# Microcontroller.net
KiCad netlist of a schematic drawn in Altium Designer
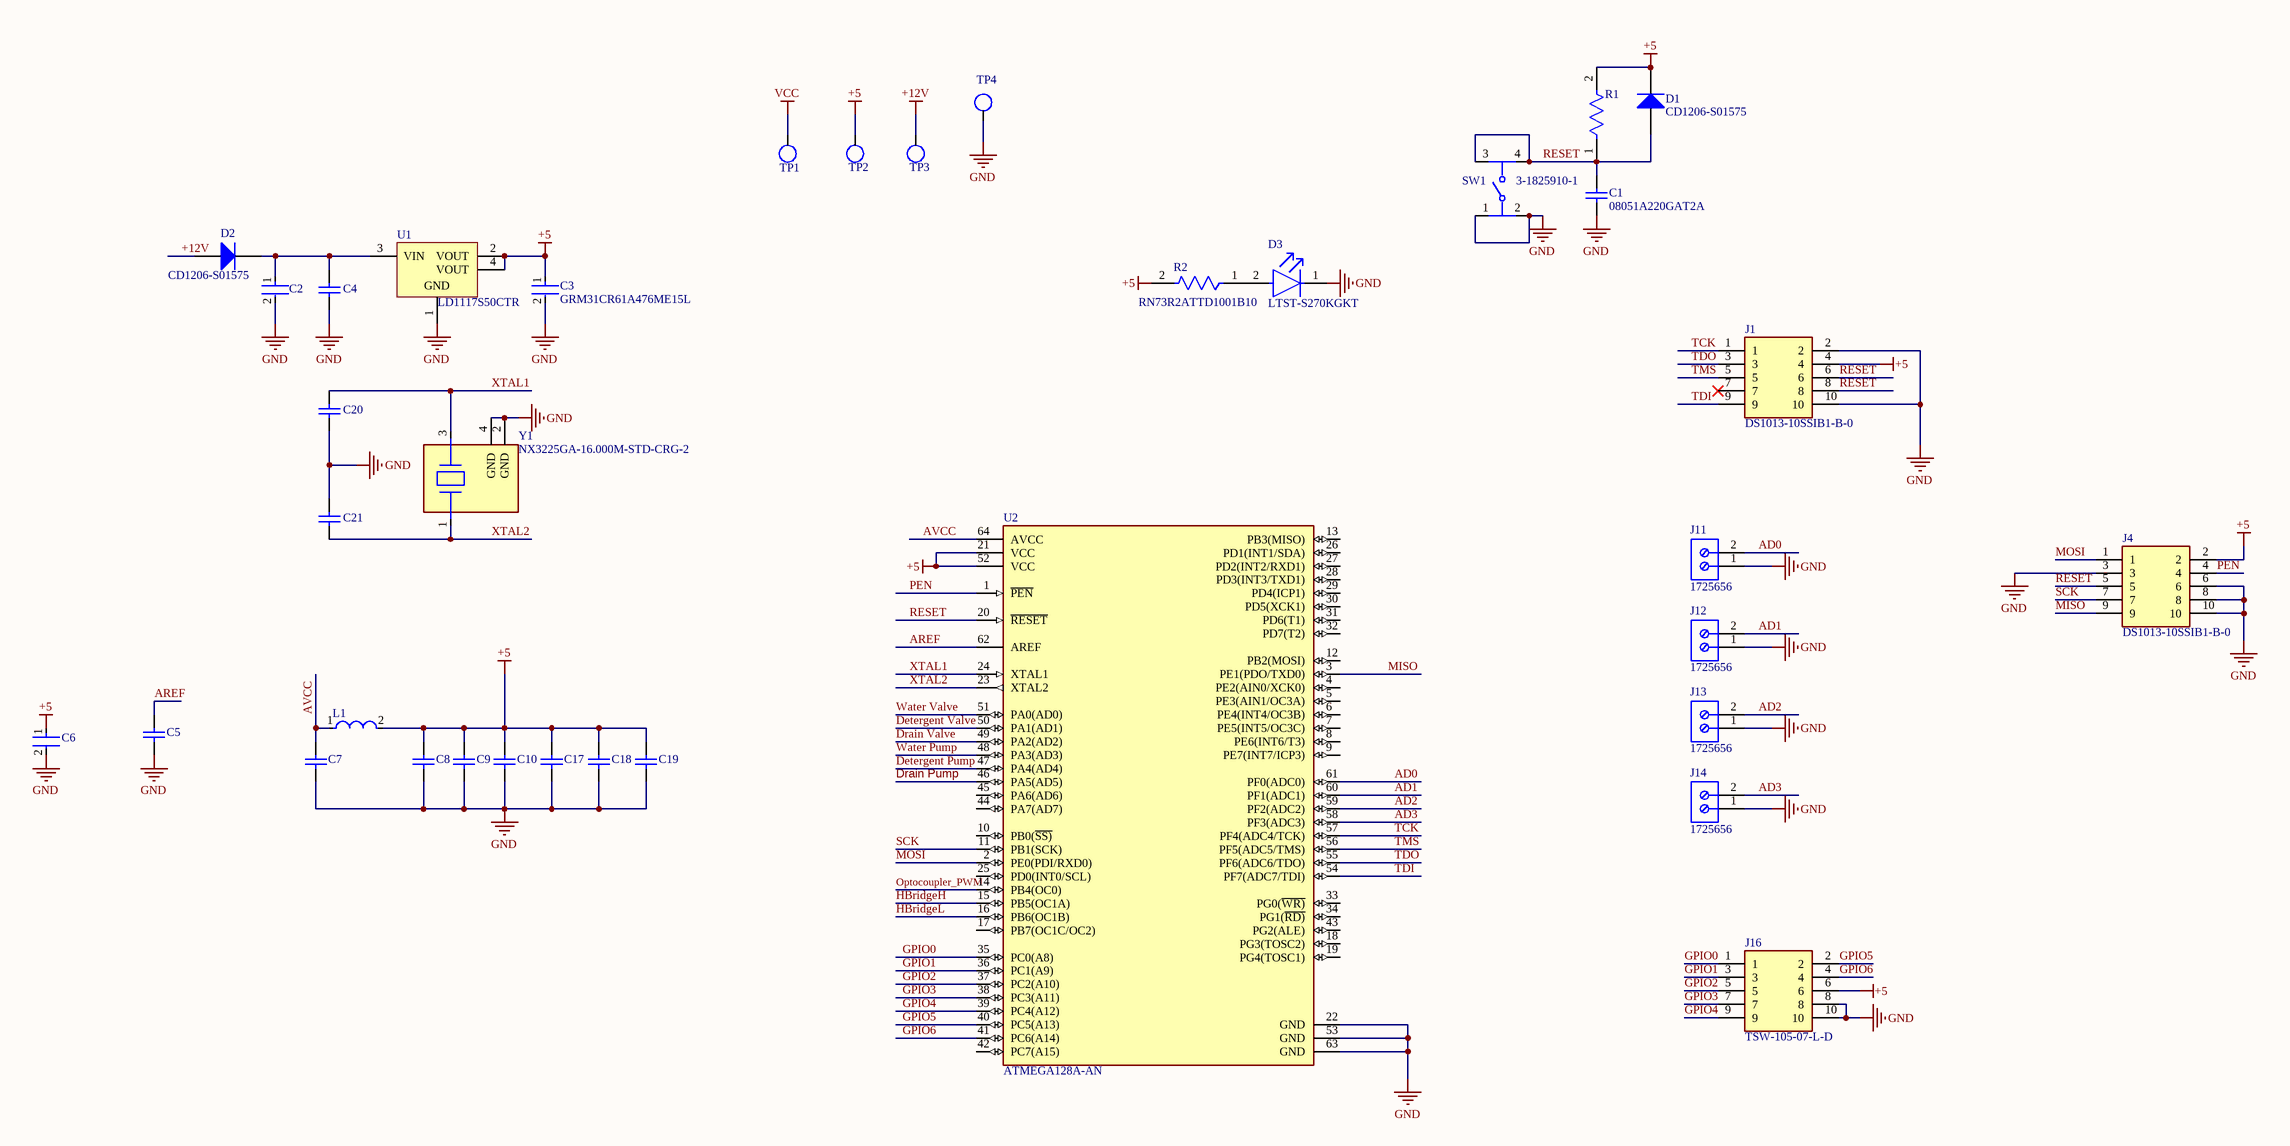
[diagram p0: Microcontroller.SchDoc]

(export (version "E")
  (design (tool "Eeschema 10.0.6"))
  (components
    (comp (ref "C1")
      (value "08051A220GAT2A")
      (footprint "CAPC2013X94X50ML20T25")
      (fields (field (name "MANUFACTURER") "AVX Interconnect / Elco"))
      (libsource (lib "Altium Content Vault") (part "CAP"))
    )
    (comp (ref "C2")
      (value "GRM31CR61A476ME15L")
      (footprint "FP-GRM31C-0_2-e0_3_0_8-IPC_B")
      (description "Chip Multilayer Ceramic Capacitors for General Purpose, 1206, 47uF, X5R, 15%, 20%, 10V")
      (fields (field (name "TOLERANCE") "20%") (field (name "VOLTAGE") "10V"))
      (libsource (lib "Altium Content Vault") (part "02cd4be3c70576c341d710602a673aa"))
    )
    (comp (ref "C3")
      (value "GRM31CR61A476ME15L")
      (footprint "FP-GRM31C-0_2-e0_3_0_8-IPC_B")
      (description "Chip Multilayer Ceramic Capacitors for General Purpose, 1206, 47uF, X5R, 15%, 20%, 10V")
      (fields (field (name "TOLERANCE") "20%") (field (name "VOLTAGE") "10V"))
      (libsource (lib "Altium Content Vault") (part "02cd4be3c70576c341d710602a673aa"))
    )
    (comp (ref "C4")
      (value "VJ0805Y104KFAAT")
      (footprint "CAPC2013X145X48NL20T23")
      (fields (field (name "MANUFACTURER") "Vitramon"))
      (libsource (lib "Altium Content Vault") (part "CAP"))
    )
    (comp (ref "C5")
      (value "CAP 100nF 100V 1206(3216)")
      (footprint "CAPC1206(3216)170_M")
      (description "CAP 100nF 100V ±5% 1206 (3216 Metric) Thickness 1.7mm SMD")
      (fields (field (name "TOLERANCE") "Â±5%"))
      (libsource (lib "Altium Content Vault") (part "CAP"))
    )
    (comp (ref "C6")
      (value "C1206C107M9PACTU")
      (footprint "FP-C1206C-EH-MFG")
      (description "CAP CER 100UF 6.3V X5R 1206")
      (fields (field (name "TOLERANCE") "2%") (field (name "VOLTAGE") "6.3V"))
      (libsource (lib "Altium Content Vault") (part "02cd4be3c70576c341d710602a673aa"))
    )
    (comp (ref "C7")
      (value "CAP 100nF 100V 1206(3216)")
      (footprint "CAPC1206(3216)170_M")
      (description "CAP 100nF 100V ±5% 1206 (3216 Metric) Thickness 1.7mm SMD")
      (fields (field (name "TOLERANCE") "Â±5%"))
      (libsource (lib "Altium Content Vault") (part "CAP"))
    )
    (comp (ref "C8")
      (value "CAP 100nF 100V 1206(3216)")
      (footprint "CAPC1206(3216)170_M")
      (description "CAP 100nF 100V ±5% 1206 (3216 Metric) Thickness 1.7mm SMD")
      (fields (field (name "TOLERANCE") "Â±5%"))
      (libsource (lib "Altium Content Vault") (part "CAP"))
    )
    (comp (ref "C9")
      (value "CAP 100nF 100V 1206(3216)")
      (footprint "CAPC1206(3216)170_M")
      (description "CAP 100nF 100V ±5% 1206 (3216 Metric) Thickness 1.7mm SMD")
      (fields (field (name "TOLERANCE") "Â±5%"))
      (libsource (lib "Altium Content Vault") (part "CAP"))
    )
    (comp (ref "C10")
      (value "CAP 100nF 100V 1206(3216)")
      (footprint "CAPC1206(3216)170_M")
      (description "CAP 100nF 100V ±5% 1206 (3216 Metric) Thickness 1.7mm SMD")
      (fields (field (name "TOLERANCE") "Â±5%"))
      (libsource (lib "Altium Content Vault") (part "CAP"))
    )
    (comp (ref "C17")
      (value "CAP 100nF 100V 1206(3216)")
      (footprint "CAPC1206(3216)170_M")
      (description "CAP 100nF 100V ±5% 1206 (3216 Metric) Thickness 1.7mm SMD")
      (fields (field (name "TOLERANCE") "Â±5%"))
      (libsource (lib "Altium Content Vault") (part "CAP"))
    )
    (comp (ref "C18")
      (value "CAP 100nF 100V 1206(3216)")
      (footprint "CAPC1206(3216)170_M")
      (description "CAP 100nF 100V ±5% 1206 (3216 Metric) Thickness 1.7mm SMD")
      (fields (field (name "TOLERANCE") "Â±5%"))
      (libsource (lib "Altium Content Vault") (part "CAP"))
    )
    (comp (ref "C19")
      (value "CAP 100nF 100V 1206(3216)")
      (footprint "CAPC1206(3216)170_M")
      (description "CAP 100nF 100V ±5% 1206 (3216 Metric) Thickness 1.7mm SMD")
      (fields (field (name "TOLERANCE") "Â±5%"))
      (libsource (lib "Altium Content Vault") (part "CAP"))
    )
    (comp (ref "C20")
      (value "VJ0805Y104KFAAT")
      (footprint "CAPC2013X145X48NL20T23")
      (fields (field (name "MANUFACTURER") "Vitramon"))
      (libsource (lib "Altium Content Vault") (part "CAP"))
    )
    (comp (ref "C21")
      (value "VJ0805Y104KFAAT")
      (footprint "CAPC2013X145X48NL20T23")
      (fields (field (name "MANUFACTURER") "Vitramon"))
      (libsource (lib "Altium Content Vault") (part "CAP"))
    )
    (comp (ref "D1")
      (value "CD1206-S01575")
      (footprint "BOUR-CD1206-S01575-2_L")
      (description "75 V Small Signal Switching Diode, 150 mA, 2.5 uA, 1026 Molded Package, RoHS, Tape and Reel")
      (fields (field (name "MANUFACTURER") "Bourns"))
      (libsource (lib "Altium Content Vault") (part "BOUR-A1K2-2"))
    )
    (comp (ref "D2")
      (value "CD1206-S01575")
      (footprint "BOUR-CD1206-S01575-2_L")
      (description "75 V Small Signal Switching Diode, 150 mA, 2.5 uA, 1026 Molded Package, RoHS, Tape and Reel")
      (fields (field (name "MANUFACTURER") "Bourns"))
      (libsource (lib "Altium Content Vault") (part "BOUR-A1K2-2"))
    )
    (comp (ref "D3")
      (value "LTST-S270KGKT")
      (footprint "FP-LTST-S270KGKT-MFG")
      (description "LED GREEN CLEAR CHIP SMD R/A")
      (libsource (lib "Altium Content Vault") (part "8706943c75ba83719d021d2fdc84c58"))
    )
    (comp (ref "J1")
      (value "DS1013-10SSIB1-B-0")
      (footprint "SamacSys:DS101310SSIB1B0")
      (description "Connector")
      (libsource (lib "*") (part "DS1013-10SSIB1-B-0"))
    )
    (comp (ref "J4")
      (value "DS1013-10SSIB1-B-0")
      (footprint "SamacSys:DS101310SSIB1B0")
      (description "Connector")
      (libsource (lib "*") (part "DS1013-10SSIB1-B-0"))
    )
    (comp (ref "J11")
      (value "1725656")
      (footprint "PHOE-1725656-2")
      (description "Male Header, Pitch 2.54 mm, 1 x 2 Position, Height 9 mm, Tail Length 3.5 mm")
      (fields (field (name "MANUFACTURER") "Phoenix Contact"))
      (libsource (lib "Altium Content Vault") (part "CN-1P-F-TB2"))
    )
    (comp (ref "J12")
      (value "1725656")
      (footprint "PHOE-1725656-2")
      (description "Male Header, Pitch 2.54 mm, 1 x 2 Position, Height 9 mm, Tail Length 3.5 mm")
      (fields (field (name "MANUFACTURER") "Phoenix Contact"))
      (libsource (lib "Altium Content Vault") (part "CN-1P-F-TB2"))
    )
    (comp (ref "J13")
      (value "1725656")
      (footprint "PHOE-1725656-2")
      (description "Male Header, Pitch 2.54 mm, 1 x 2 Position, Height 9 mm, Tail Length 3.5 mm")
      (fields (field (name "MANUFACTURER") "Phoenix Contact"))
      (libsource (lib "Altium Content Vault") (part "CN-1P-F-TB2"))
    )
    (comp (ref "J14")
      (value "1725656")
      (footprint "PHOE-1725656-2")
      (description "Male Header, Pitch 2.54 mm, 1 x 2 Position, Height 9 mm, Tail Length 3.5 mm")
      (fields (field (name "MANUFACTURER") "Phoenix Contact"))
      (libsource (lib "Altium Content Vault") (part "CN-1P-F-TB2"))
    )
    (comp (ref "J16")
      (value "TSW-105-07-L-D")
      (footprint "SamacSys:TSW-105-XX-YY-D")
      (description "Connector")
      (fields (field (name "MOUSER PART NUMBER") "200-TSW10507LD"))
      (libsource (lib "*") (part "TSW-105-07-L-D"))
    )
    (comp (ref "L1")
      (value "MLZ2012N100LTD25")
      (footprint "FP-MLZ2012-1_25-MFG")
      (description "Shielded Multilayer Inductor 10uH ±20% 500mA 390mΩ AEC-Q200 SMD 0805")
      (fields (field (name "TOLERANCE") "20%"))
      (libsource (lib "Altium Content Vault") (part "725321dda6339637d4d059423bc1c3c"))
    )
    (comp (ref "R1")
      (value "RN73C2A10KLTDF")
      (footprint "FP-RN732A-MFG")
      (description "SMD Chip Resistor, Thin Film, 10.LKΩ, 100 V, 0805 [2012 Metric], 100 mW, 0.1%, RN73 Series")
      (fields
        (field (name "OCTOPART") "https://octopart.com/rn73c2a10kltdf-te+connectivity-22738657")
        (field (name "TOLERANCE") "42")
      )
      (libsource (lib "Altium Content Vault") (part "1029c3af85768c4190bb7ad29bc67b5"))
    )
    (comp (ref "R2")
      (value "RN73R2ATTD1001B10")
      (footprint "FP-RN73R2A-IPC_A")
      (description "1kΩ ±0.1% 0.125W, 1/8W Chip Resistor 0805 (2012 Metric) Moisture Resistant Thin Film")
      (libsource (lib "Altium Content Vault") (part "1029c3af85768c4190bb7ad29bc67b5"))
    )
    (comp (ref "SW1")
      (value "3-1825910-1")
      (footprint "FP-3-1825910-1-MFG")
      (description "SWITCH TACTILE SPST-NO 0.05A 24V")
      (fields
        (field (name "MANUFACTURER") "TE Connectivity")
        (field (name "OCTOPART") "https://octopart.com/3-1825910-1-te+connectivity-46506874")
      )
      (libsource (lib "Altium Content Vault") (part "b8895f3f4cefb76e1819d2863dba89b"))
    )
    (comp (ref "TP1")
      (value "testpoint")
      (footprint "testpoint")
      (libsource (lib "Schlib1") (part "testpoint"))
    )
    (comp (ref "TP2")
      (value "testpoint")
      (footprint "testpoint")
      (libsource (lib "Schlib1") (part "testpoint"))
    )
    (comp (ref "TP3")
      (value "testpoint")
      (footprint "testpoint")
      (libsource (lib "Schlib1") (part "testpoint"))
    )
    (comp (ref "TP4")
      (value "testpoint")
      (footprint "testpoint")
      (libsource (lib "Schlib1") (part "testpoint"))
    )
    (comp (ref "U1")
      (value "LD1117S50CTR")
      (footprint "SOT-223_N")
      (description "Fixed Low Drop Positive Voltage Regulator, 5V, 4-Pin SOT-223, Tape and Reel")
      (libsource (lib "Altium Content Vault") (part "PM-REG-LD1117-SOT4"))
    )
    (comp (ref "U2")
      (value "ATMEGA128A-AN")
      (footprint "FP-64A-MFG")
      (libsource (lib "Altium Content Vault") (part "c0534164f6da0610d730194d2b549ec"))
    )
    (comp (ref "Y1")
      (value "NX3225GA-16.000M-STD-CRG-2")
      (footprint "FP-NX3225GA-MFG")
      (description "CRYSTAL 16.0000MHZ 8PF SMD")
      (libsource (lib "Altium Content Vault") (part "6320effb7d3e443b36bf79d8ebe02e5"))
    )
  )
  (nets
    (net (code "1") (name "+5") (class "Default")
      (node (ref "C10") (pin "2") (pinfunction "2_2") (pintype "passive"))
      (node (ref "C17") (pin "2") (pinfunction "2_2") (pintype "passive"))
      (node (ref "C18") (pin "2") (pinfunction "2_2") (pintype "passive"))
      (node (ref "C19") (pin "2") (pinfunction "2_2") (pintype "passive"))
      (node (ref "C3") (pin "1") (pinfunction "1_1") (pintype "passive"))
      (node (ref "C6") (pin "1") (pinfunction "1_1") (pintype "passive"))
      (node (ref "C8") (pin "2") (pinfunction "2_2") (pintype "passive"))
      (node (ref "C9") (pin "2") (pinfunction "2_2") (pintype "passive"))
      (node (ref "D1") (pin "2") (pinfunction "K_2") (pintype "passive"))
      (node (ref "J1") (pin "4") (pinfunction "4_4") (pintype "passive"))
      (node (ref "J16") (pin "6") (pinfunction "6_6") (pintype "passive"))
      (node (ref "J4") (pin "2") (pinfunction "2_2") (pintype "passive"))
      (node (ref "L1") (pin "2") (pinfunction "2_2") (pintype "passive"))
      (node (ref "R1") (pin "2") (pinfunction "2_2") (pintype "passive"))
      (node (ref "R2") (pin "2") (pinfunction "2_2") (pintype "passive"))
      (node (ref "TP2") (pin "1") (pinfunction "1_1") (pintype "passive"))
      (node (ref "U1") (pin "2") (pinfunction "VOUT_2") (pintype "power_in"))
      (node (ref "U1") (pin "4") (pinfunction "VOUT_4") (pintype "power_in"))
      (node (ref "U2") (pin "21") (pinfunction "VCC_21") (pintype "power_in"))
      (node (ref "U2") (pin "52") (pinfunction "VCC_52") (pintype "power_in"))
    )
    (net (code "2") (name "+12V") (class "Default")
      (node (ref "D2") (pin "1") (pinfunction "A_1") (pintype "passive"))
      (node (ref "TP3") (pin "1") (pinfunction "1_1") (pintype "passive"))
    )
    (net (code "3") (name "/AD0") (class "Default")
      (node (ref "J11") (pin "2") (pinfunction "2_2") (pintype "passive"))
      (node (ref "U2") (pin "61") (pinfunction "PF0(ADC0)_61") (pintype "bidirectional"))
    )
    (net (code "4") (name "/AD1") (class "Default")
      (node (ref "J12") (pin "2") (pinfunction "2_2") (pintype "passive"))
      (node (ref "U2") (pin "60") (pinfunction "PF1(ADC1)_60") (pintype "bidirectional"))
    )
    (net (code "5") (name "/AD2") (class "Default")
      (node (ref "J13") (pin "2") (pinfunction "2_2") (pintype "passive"))
      (node (ref "U2") (pin "59") (pinfunction "PF2(ADC2)_59") (pintype "bidirectional"))
    )
    (net (code "6") (name "/AD3") (class "Default")
      (node (ref "J14") (pin "2") (pinfunction "2_2") (pintype "passive"))
      (node (ref "U2") (pin "58") (pinfunction "PF3(ADC3)_58") (pintype "bidirectional"))
    )
    (net (code "7") (name "/AREF") (class "Default")
      (node (ref "C5") (pin "2") (pinfunction "2_2") (pintype "passive"))
      (node (ref "U2") (pin "62") (pinfunction "AREF_62") (pintype "passive"))
    )
    (net (code "8") (name "/AVCC") (class "Default")
      (node (ref "C7") (pin "2") (pinfunction "2_2") (pintype "passive"))
      (node (ref "L1") (pin "1") (pinfunction "1_1") (pintype "passive"))
      (node (ref "U2") (pin "64") (pinfunction "AVCC_64") (pintype "power_in"))
    )
    (net (code "9") (name "/Detergent Pump") (class "Default")
      (node (ref "U2") (pin "47") (pinfunction "PA4(AD4)_47") (pintype "bidirectional"))
    )
    (net (code "10") (name "/Detergent Valve") (class "Default")
      (node (ref "U2") (pin "50") (pinfunction "PA1(AD1)_50") (pintype "bidirectional"))
    )
    (net (code "11") (name "/Drain Pump") (class "Default")
      (node (ref "U2") (pin "46") (pinfunction "PA5(AD5)_46") (pintype "bidirectional"))
    )
    (net (code "12") (name "/Drain Valve") (class "Default")
      (node (ref "U2") (pin "49") (pinfunction "PA2(AD2)_49") (pintype "bidirectional"))
    )
    (net (code "13") (name "/GPIO0") (class "Default")
      (node (ref "J16") (pin "1") (pinfunction "1_1") (pintype "passive"))
      (node (ref "U2") (pin "35") (pinfunction "PC0(A8)_35") (pintype "bidirectional"))
    )
    (net (code "14") (name "/GPIO1") (class "Default")
      (node (ref "J16") (pin "3") (pinfunction "3_3") (pintype "passive"))
      (node (ref "U2") (pin "36") (pinfunction "PC1(A9)_36") (pintype "bidirectional"))
    )
    (net (code "15") (name "/GPIO2") (class "Default")
      (node (ref "J16") (pin "5") (pinfunction "5_5") (pintype "passive"))
      (node (ref "U2") (pin "37") (pinfunction "PC2(A10)_37") (pintype "bidirectional"))
    )
    (net (code "16") (name "/GPIO3") (class "Default")
      (node (ref "J16") (pin "7") (pinfunction "7_7") (pintype "passive"))
      (node (ref "U2") (pin "38") (pinfunction "PC3(A11)_38") (pintype "bidirectional"))
    )
    (net (code "17") (name "/GPIO4") (class "Default")
      (node (ref "J16") (pin "9") (pinfunction "9_9") (pintype "passive"))
      (node (ref "U2") (pin "39") (pinfunction "PC4(A12)_39") (pintype "bidirectional"))
    )
    (net (code "18") (name "/GPIO5") (class "Default")
      (node (ref "J16") (pin "2") (pinfunction "2_2") (pintype "passive"))
      (node (ref "U2") (pin "40") (pinfunction "PC5(A13)_40") (pintype "bidirectional"))
    )
    (net (code "19") (name "/GPIO6") (class "Default")
      (node (ref "J16") (pin "4") (pinfunction "4_4") (pintype "passive"))
      (node (ref "U2") (pin "41") (pinfunction "PC6(A14)_41") (pintype "bidirectional"))
    )
    (net (code "20") (name "/HBridgeH") (class "Default")
      (node (ref "U2") (pin "15") (pinfunction "PB5(OC1A)_15") (pintype "bidirectional"))
    )
    (net (code "21") (name "/HBridgeL") (class "Default")
      (node (ref "U2") (pin "16") (pinfunction "PB6(OC1B)_16") (pintype "bidirectional"))
    )
    (net (code "22") (name "/MISO") (class "Default")
      (node (ref "J4") (pin "9") (pinfunction "9_9") (pintype "passive"))
      (node (ref "U2") (pin "3") (pinfunction "PE1(PDO/TXD0)_3") (pintype "bidirectional"))
    )
    (net (code "23") (name "/MOSI") (class "Default")
      (node (ref "J4") (pin "1") (pinfunction "1_1") (pintype "passive"))
      (node (ref "U2") (pin "2") (pinfunction "PE0(PDI/RXD0)_2") (pintype "bidirectional"))
    )
    (net (code "24") (name "/Optocoupler_PWM") (class "Default")
      (node (ref "U2") (pin "14") (pinfunction "PB4(OC0)_14") (pintype "bidirectional"))
    )
    (net (code "25") (name "/PEN") (class "Default")
      (node (ref "J4") (pin "4") (pinfunction "4_4") (pintype "passive"))
      (node (ref "U2") (pin "1") (pinfunction "~{PEN}_1") (pintype "input"))
    )
    (net (code "26") (name "/RESET") (class "Default")
      (node (ref "C1") (pin "2") (pinfunction "2_2") (pintype "passive"))
      (node (ref "D1") (pin "1") (pinfunction "A_1") (pintype "passive"))
      (node (ref "J1") (pin "6") (pinfunction "6_6") (pintype "passive"))
      (node (ref "J1") (pin "8") (pinfunction "8_8") (pintype "passive"))
      (node (ref "J4") (pin "5") (pinfunction "5_5") (pintype "passive"))
      (node (ref "R1") (pin "1") (pinfunction "1_1") (pintype "passive"))
      (node (ref "SW1") (pin "3") (pinfunction "3_3") (pintype "passive"))
      (node (ref "SW1") (pin "4") (pinfunction "4_4") (pintype "passive"))
      (node (ref "U2") (pin "20") (pinfunction "~{RESET}_20") (pintype "input"))
    )
    (net (code "27") (name "/SCK") (class "Default")
      (node (ref "J4") (pin "7") (pinfunction "7_7") (pintype "passive"))
      (node (ref "U2") (pin "11") (pinfunction "PB1(SCK)_11") (pintype "bidirectional"))
    )
    (net (code "28") (name "/TCK") (class "Default")
      (node (ref "J1") (pin "1") (pinfunction "1_1") (pintype "passive"))
      (node (ref "U2") (pin "57") (pinfunction "PF4(ADC4/TCK)_57") (pintype "bidirectional"))
    )
    (net (code "29") (name "/TDI") (class "Default")
      (node (ref "J1") (pin "9") (pinfunction "9_9") (pintype "passive"))
      (node (ref "U2") (pin "54") (pinfunction "PF7(ADC7/TDI)_54") (pintype "bidirectional"))
    )
    (net (code "30") (name "/TDO") (class "Default")
      (node (ref "J1") (pin "3") (pinfunction "3_3") (pintype "passive"))
      (node (ref "U2") (pin "55") (pinfunction "PF6(ADC6/TDO)_55") (pintype "bidirectional"))
    )
    (net (code "31") (name "/TMS") (class "Default")
      (node (ref "J1") (pin "5") (pinfunction "5_5") (pintype "passive"))
      (node (ref "U2") (pin "56") (pinfunction "PF5(ADC5/TMS)_56") (pintype "bidirectional"))
    )
    (net (code "32") (name "/Water Pump") (class "Default")
      (node (ref "U2") (pin "48") (pinfunction "PA3(AD3)_48") (pintype "bidirectional"))
    )
    (net (code "33") (name "/Water Valve") (class "Default")
      (node (ref "U2") (pin "51") (pinfunction "PA0(AD0)_51") (pintype "bidirectional"))
    )
    (net (code "34") (name "/XTAL1") (class "Default")
      (node (ref "C20") (pin "2") (pinfunction "2_2") (pintype "passive"))
      (node (ref "U2") (pin "24") (pinfunction "XTAL1_24") (pintype "input"))
      (node (ref "Y1") (pin "3") (pinfunction "3_3") (pintype "passive"))
    )
    (net (code "35") (name "/XTAL2") (class "Default")
      (node (ref "C21") (pin "1") (pinfunction "1_1") (pintype "passive"))
      (node (ref "U2") (pin "23") (pinfunction "XTAL2_23") (pintype "output"))
      (node (ref "Y1") (pin "1") (pinfunction "1_1") (pintype "passive"))
    )
    (net (code "36") (name "GND") (class "Default")
      (node (ref "C1") (pin "1") (pinfunction "1_1") (pintype "passive"))
      (node (ref "C10") (pin "1") (pinfunction "1_1") (pintype "passive"))
      (node (ref "C17") (pin "1") (pinfunction "1_1") (pintype "passive"))
      (node (ref "C18") (pin "1") (pinfunction "1_1") (pintype "passive"))
      (node (ref "C19") (pin "1") (pinfunction "1_1") (pintype "passive"))
      (node (ref "C2") (pin "2") (pinfunction "2_2") (pintype "passive"))
      (node (ref "C20") (pin "1") (pinfunction "1_1") (pintype "passive"))
      (node (ref "C21") (pin "2") (pinfunction "2_2") (pintype "passive"))
      (node (ref "C3") (pin "2") (pinfunction "2_2") (pintype "passive"))
      (node (ref "C4") (pin "1") (pinfunction "1_1") (pintype "passive"))
      (node (ref "C5") (pin "1") (pinfunction "1_1") (pintype "passive"))
      (node (ref "C6") (pin "2") (pinfunction "2_2") (pintype "passive"))
      (node (ref "C7") (pin "1") (pinfunction "1_1") (pintype "passive"))
      (node (ref "C8") (pin "1") (pinfunction "1_1") (pintype "passive"))
      (node (ref "C9") (pin "1") (pinfunction "1_1") (pintype "passive"))
      (node (ref "D3") (pin "1") (pinfunction "C_1") (pintype "passive"))
      (node (ref "J1") (pin "10") (pinfunction "10_10") (pintype "passive"))
      (node (ref "J1") (pin "2") (pinfunction "2_2") (pintype "passive"))
      (node (ref "J11") (pin "1") (pinfunction "1_1") (pintype "passive"))
      (node (ref "J12") (pin "1") (pinfunction "1_1") (pintype "passive"))
      (node (ref "J13") (pin "1") (pinfunction "1_1") (pintype "passive"))
      (node (ref "J14") (pin "1") (pinfunction "1_1") (pintype "passive"))
      (node (ref "J16") (pin "10") (pinfunction "10_10") (pintype "passive"))
      (node (ref "J16") (pin "8") (pinfunction "8_8") (pintype "passive"))
      (node (ref "J4") (pin "10") (pinfunction "10_10") (pintype "passive"))
      (node (ref "J4") (pin "3") (pinfunction "3_3") (pintype "passive"))
      (node (ref "J4") (pin "6") (pinfunction "6_6") (pintype "passive"))
      (node (ref "J4") (pin "8") (pinfunction "8_8") (pintype "passive"))
      (node (ref "SW1") (pin "1") (pinfunction "1_1") (pintype "passive"))
      (node (ref "SW1") (pin "2") (pinfunction "2_2") (pintype "passive"))
      (node (ref "TP4") (pin "1") (pinfunction "1_1") (pintype "passive"))
      (node (ref "U1") (pin "1") (pinfunction "GND_1") (pintype "power_in"))
      (node (ref "U2") (pin "22") (pinfunction "GND_22") (pintype "power_in"))
      (node (ref "U2") (pin "53") (pinfunction "GND_53") (pintype "power_in"))
      (node (ref "U2") (pin "63") (pinfunction "GND_63") (pintype "power_in"))
      (node (ref "Y1") (pin "2") (pinfunction "GND_2") (pintype "power_in"))
      (node (ref "Y1") (pin "4") (pinfunction "GND_4") (pintype "power_in"))
    )
    (net (code "37") (name "Net-(D2-K)") (class "Default")
      (node (ref "C2") (pin "1") (pinfunction "1_1") (pintype "passive"))
      (node (ref "C4") (pin "2") (pinfunction "2_2") (pintype "passive"))
      (node (ref "D2") (pin "2") (pinfunction "K_2") (pintype "passive"))
      (node (ref "U1") (pin "3") (pinfunction "VIN_3") (pintype "power_in"))
    )
    (net (code "38") (name "Net-(D3-A)") (class "Default")
      (node (ref "D3") (pin "2") (pinfunction "A_2") (pintype "passive"))
      (node (ref "R2") (pin "1") (pinfunction "1_1") (pintype "passive"))
    )
    (net (code "39") (name "VCC") (class "Default")
      (node (ref "TP1") (pin "1") (pinfunction "1_1") (pintype "passive"))
    )
    (net (code "40") (name "unconnected-(J1-Pad7)") (class "Default")
      (node (ref "J1") (pin "7") (pinfunction "7_7") (pintype "passive+no_connect"))
    )
    (net (code "41") (name "unconnected-(U2-PA6(AD6)-Pad45)") (class "Default")
      (node (ref "U2") (pin "45") (pinfunction "PA6(AD6)_45") (pintype "bidirectional"))
    )
    (net (code "42") (name "unconnected-(U2-PA7(AD7)-Pad44)") (class "Default")
      (node (ref "U2") (pin "44") (pinfunction "PA7(AD7)_44") (pintype "bidirectional"))
    )
    (net (code "43") (name "unconnected-(U2-PB0(~{SS)}-Pad10)") (class "Default")
      (node (ref "U2") (pin "10") (pinfunction "PB0(~{SS)}_10") (pintype "bidirectional"))
    )
    (net (code "44") (name "unconnected-(U2-PB2(MOSI)-Pad12)") (class "Default")
      (node (ref "U2") (pin "12") (pinfunction "PB2(MOSI)_12") (pintype "bidirectional"))
    )
    (net (code "45") (name "unconnected-(U2-PB3(MISO)-Pad13)") (class "Default")
      (node (ref "U2") (pin "13") (pinfunction "PB3(MISO)_13") (pintype "bidirectional"))
    )
    (net (code "46") (name "unconnected-(U2-PB7(OC1C{slash}OC2)-Pad17)") (class "Default")
      (node (ref "U2") (pin "17") (pinfunction "PB7(OC1C/OC2)_17") (pintype "bidirectional"))
    )
    (net (code "47") (name "unconnected-(U2-PC7(A15)-Pad42)") (class "Default")
      (node (ref "U2") (pin "42") (pinfunction "PC7(A15)_42") (pintype "bidirectional"))
    )
    (net (code "48") (name "unconnected-(U2-PD0(INT0{slash}SCL)-Pad25)") (class "Default")
      (node (ref "U2") (pin "25") (pinfunction "PD0(INT0/SCL)_25") (pintype "bidirectional"))
    )
    (net (code "49") (name "unconnected-(U2-PD1(INT1{slash}SDA)-Pad26)") (class "Default")
      (node (ref "U2") (pin "26") (pinfunction "PD1(INT1/SDA)_26") (pintype "bidirectional"))
    )
    (net (code "50") (name "unconnected-(U2-PD2(INT2{slash}RXD1)-Pad27)") (class "Default")
      (node (ref "U2") (pin "27") (pinfunction "PD2(INT2/RXD1)_27") (pintype "bidirectional"))
    )
    (net (code "51") (name "unconnected-(U2-PD3(INT3{slash}TXD1)-Pad28)") (class "Default")
      (node (ref "U2") (pin "28") (pinfunction "PD3(INT3/TXD1)_28") (pintype "bidirectional"))
    )
    (net (code "52") (name "unconnected-(U2-PD4(ICP1)-Pad29)") (class "Default")
      (node (ref "U2") (pin "29") (pinfunction "PD4(ICP1)_29") (pintype "bidirectional"))
    )
    (net (code "53") (name "unconnected-(U2-PD5(XCK1)-Pad30)") (class "Default")
      (node (ref "U2") (pin "30") (pinfunction "PD5(XCK1)_30") (pintype "bidirectional"))
    )
    (net (code "54") (name "unconnected-(U2-PD6(T1)-Pad31)") (class "Default")
      (node (ref "U2") (pin "31") (pinfunction "PD6(T1)_31") (pintype "bidirectional"))
    )
    (net (code "55") (name "unconnected-(U2-PD7(T2)-Pad32)") (class "Default")
      (node (ref "U2") (pin "32") (pinfunction "PD7(T2)_32") (pintype "bidirectional"))
    )
    (net (code "56") (name "unconnected-(U2-PE2(AIN0{slash}XCK0)-Pad4)") (class "Default")
      (node (ref "U2") (pin "4") (pinfunction "PE2(AIN0/XCK0)_4") (pintype "bidirectional"))
    )
    (net (code "57") (name "unconnected-(U2-PE3(AIN1{slash}OC3A)-Pad5)") (class "Default")
      (node (ref "U2") (pin "5") (pinfunction "PE3(AIN1/OC3A)_5") (pintype "bidirectional"))
    )
    (net (code "58") (name "unconnected-(U2-PE4(INT4{slash}OC3B)-Pad6)") (class "Default")
      (node (ref "U2") (pin "6") (pinfunction "PE4(INT4/OC3B)_6") (pintype "bidirectional"))
    )
    (net (code "59") (name "unconnected-(U2-PE5(INT5{slash}OC3C)-Pad7)") (class "Default")
      (node (ref "U2") (pin "7") (pinfunction "PE5(INT5/OC3C)_7") (pintype "bidirectional"))
    )
    (net (code "60") (name "unconnected-(U2-PE6(INT6{slash}T3)-Pad8)") (class "Default")
      (node (ref "U2") (pin "8") (pinfunction "PE6(INT6/T3)_8") (pintype "bidirectional"))
    )
    (net (code "61") (name "unconnected-(U2-PE7(INT7{slash}ICP3)-Pad9)") (class "Default")
      (node (ref "U2") (pin "9") (pinfunction "PE7(INT7/ICP3)_9") (pintype "bidirectional"))
    )
    (net (code "62") (name "unconnected-(U2-PG0(~{WR)}-Pad33)") (class "Default")
      (node (ref "U2") (pin "33") (pinfunction "PG0(~{WR)}_33") (pintype "bidirectional"))
    )
    (net (code "63") (name "unconnected-(U2-PG1(~{RD)}-Pad34)") (class "Default")
      (node (ref "U2") (pin "34") (pinfunction "PG1(~{RD)}_34") (pintype "bidirectional"))
    )
    (net (code "64") (name "unconnected-(U2-PG2(ALE)-Pad43)") (class "Default")
      (node (ref "U2") (pin "43") (pinfunction "PG2(ALE)_43") (pintype "bidirectional"))
    )
    (net (code "65") (name "unconnected-(U2-PG3(TOSC2)-Pad18)") (class "Default")
      (node (ref "U2") (pin "18") (pinfunction "PG3(TOSC2)_18") (pintype "bidirectional"))
    )
    (net (code "66") (name "unconnected-(U2-PG4(TOSC1)-Pad19)") (class "Default")
      (node (ref "U2") (pin "19") (pinfunction "PG4(TOSC1)_19") (pintype "bidirectional"))
    )
  )
)
